# UCirKitUserStudy4.net
KiCad netlist of a schematic drawn in EAGLE
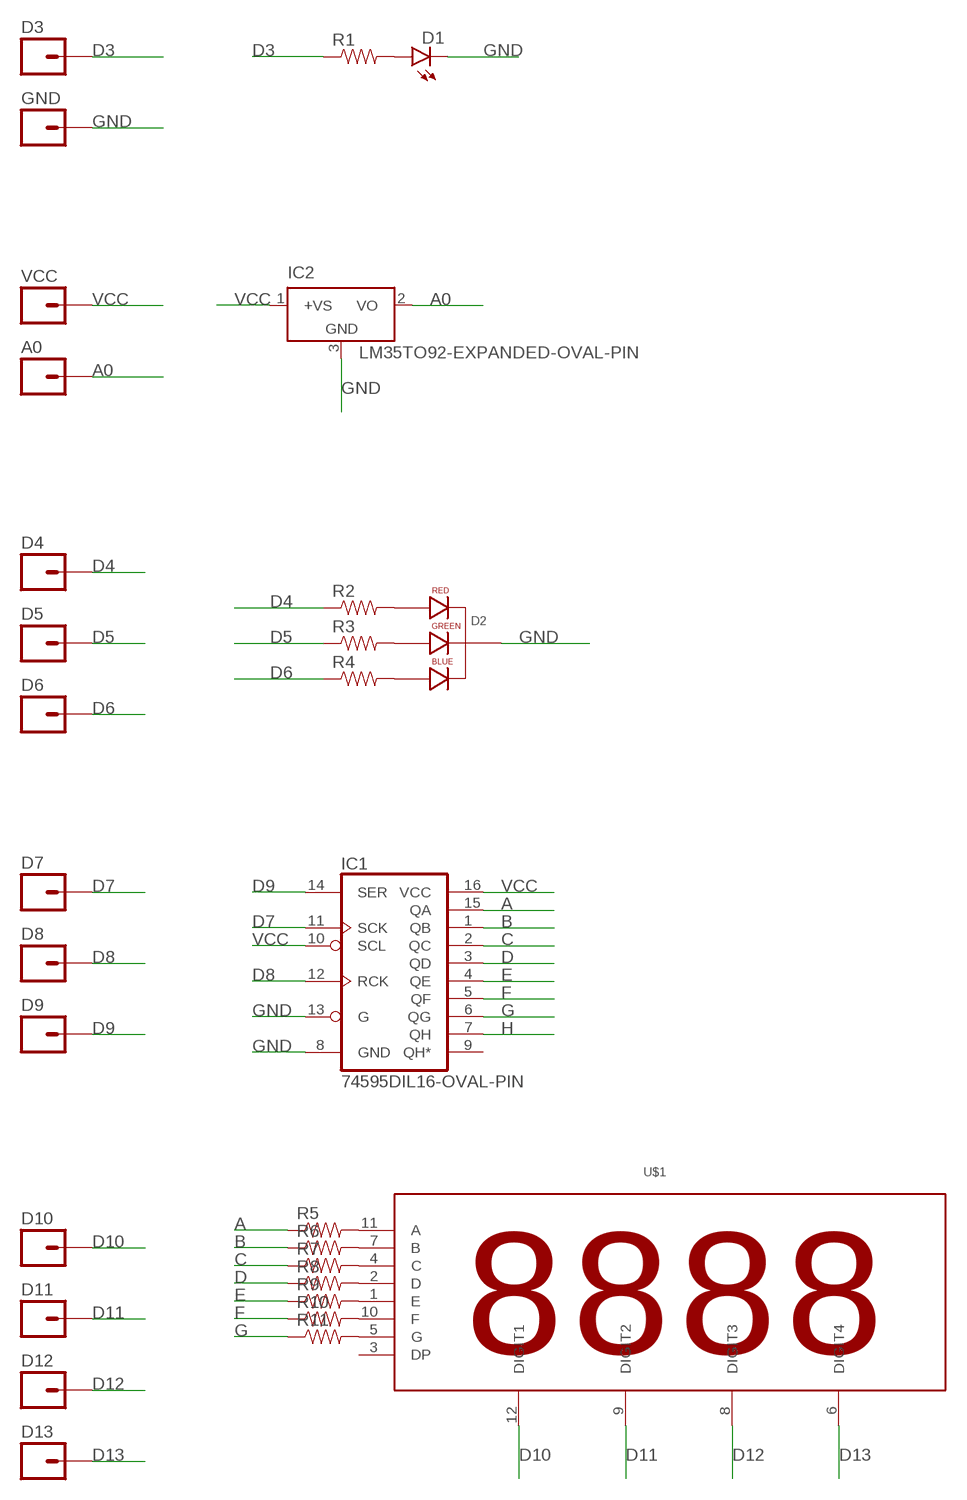
[diagram p0: schematic, sheet 1]

(export (version "E")
  (design (tool "Eeschema 10.0.6"))
  (components
    (comp (ref "A0")
      (value "M01OVAL_PIN")
      (footprint "eagle-import:1X01_OVAL_PIN")
      (libsource (lib "eagle-import") (part "M01OVAL_PIN"))
    )
    (comp (ref "D1")
      (value "LEDLED3MM-EXPANDED-OVAL-PIN")
      (footprint "eagle-import:LED3MM-EXPANDED-OVAL-PIN")
      (libsource (lib "eagle-import") (part "LEDLED3MM-EXPANDED-OVAL-PIN"))
    )
    (comp (ref "D2")
      (value "LED-RGB-CC-THRULED-RGB-THRU-EXPANDED-OVAL-PIN")
      (footprint "eagle-import:LED-RGB-THRU-EXPANDED-OVAL-PIN")
      (libsource (lib "eagle-import") (part "LED-RGB-CC-THRULED-RGB-THRU-EXPANDED-OVAL-PIN"))
    )
    (comp (ref "D3")
      (value "M01OVAL_PIN")
      (footprint "eagle-import:1X01_OVAL_PIN")
      (libsource (lib "eagle-import") (part "M01OVAL_PIN"))
    )
    (comp (ref "D4")
      (value "M01OVAL_PIN")
      (footprint "eagle-import:1X01_OVAL_PIN")
      (libsource (lib "eagle-import") (part "M01OVAL_PIN"))
    )
    (comp (ref "D5")
      (value "M01OVAL_PIN")
      (footprint "eagle-import:1X01_OVAL_PIN")
      (libsource (lib "eagle-import") (part "M01OVAL_PIN"))
    )
    (comp (ref "D6")
      (value "M01OVAL_PIN")
      (footprint "eagle-import:1X01_OVAL_PIN")
      (libsource (lib "eagle-import") (part "M01OVAL_PIN"))
    )
    (comp (ref "D7")
      (value "M01OVAL_PIN")
      (footprint "eagle-import:1X01_OVAL_PIN")
      (libsource (lib "eagle-import") (part "M01OVAL_PIN"))
    )
    (comp (ref "D8")
      (value "M01OVAL_PIN")
      (footprint "eagle-import:1X01_OVAL_PIN")
      (libsource (lib "eagle-import") (part "M01OVAL_PIN"))
    )
    (comp (ref "D9")
      (value "M01OVAL_PIN")
      (footprint "eagle-import:1X01_OVAL_PIN")
      (libsource (lib "eagle-import") (part "M01OVAL_PIN"))
    )
    (comp (ref "D10")
      (value "M01OVAL_PIN")
      (footprint "eagle-import:1X01_OVAL_PIN")
      (libsource (lib "eagle-import") (part "M01OVAL_PIN"))
    )
    (comp (ref "D11")
      (value "M01OVAL_PIN")
      (footprint "eagle-import:1X01_OVAL_PIN")
      (libsource (lib "eagle-import") (part "M01OVAL_PIN"))
    )
    (comp (ref "D12")
      (value "M01OVAL_PIN")
      (footprint "eagle-import:1X01_OVAL_PIN")
      (libsource (lib "eagle-import") (part "M01OVAL_PIN"))
    )
    (comp (ref "D13")
      (value "M01OVAL_PIN")
      (footprint "eagle-import:1X01_OVAL_PIN")
      (libsource (lib "eagle-import") (part "M01OVAL_PIN"))
    )
    (comp (ref "GND")
      (value "M01OVAL_PIN")
      (footprint "eagle-import:1X01_OVAL_PIN")
      (libsource (lib "eagle-import") (part "M01OVAL_PIN"))
    )
    (comp (ref "IC1")
      (value "74595DIL16-OVAL-PIN")
      (footprint "eagle-import:DIL16-OVAL-PIN")
      (libsource (lib "eagle-import") (part "74595DIL16-OVAL-PIN"))
    )
    (comp (ref "IC2")
      (value "LM35TO92-EXPANDED-OVAL-PIN")
      (footprint "eagle-import:TO92-EXPANDED-OVAL-PIN")
      (libsource (lib "eagle-import") (part "LM35TO92-EXPANDED-OVAL-PIN"))
    )
    (comp (ref "R1")
      (value "1KOHM-1/4W-1%(PTH)PTH-EXPANDED-OVAL-PIN")
      (footprint "eagle-import:PTH-EXPANDED-OVAL-PIN")
      (libsource (lib "eagle-import") (part "1KOHM-1/4W-1%(PTH)PTH-EXPANDED-OVAL-PIN"))
    )
    (comp (ref "R2")
      (value "1KOHM-1/4W-1%(PTH)PTH-EXPANDED-OVAL-PIN")
      (footprint "eagle-import:PTH-EXPANDED-OVAL-PIN")
      (libsource (lib "eagle-import") (part "1KOHM-1/4W-1%(PTH)PTH-EXPANDED-OVAL-PIN"))
    )
    (comp (ref "R3")
      (value "1KOHM-1/4W-1%(PTH)PTH-EXPANDED-OVAL-PIN")
      (footprint "eagle-import:PTH-EXPANDED-OVAL-PIN")
      (libsource (lib "eagle-import") (part "1KOHM-1/4W-1%(PTH)PTH-EXPANDED-OVAL-PIN"))
    )
    (comp (ref "R4")
      (value "1KOHM-1/4W-1%(PTH)PTH-EXPANDED-OVAL-PIN")
      (footprint "eagle-import:PTH-EXPANDED-OVAL-PIN")
      (libsource (lib "eagle-import") (part "1KOHM-1/4W-1%(PTH)PTH-EXPANDED-OVAL-PIN"))
    )
    (comp (ref "R5")
      (value "1KOHM-1/4W-1%(PTH)PTH-EXPANDED-OVAL-PIN")
      (footprint "eagle-import:PTH-EXPANDED-OVAL-PIN")
      (libsource (lib "eagle-import") (part "1KOHM-1/4W-1%(PTH)PTH-EXPANDED-OVAL-PIN"))
    )
    (comp (ref "R6")
      (value "1KOHM-1/4W-1%(PTH)PTH-EXPANDED-OVAL-PIN")
      (footprint "eagle-import:PTH-EXPANDED-OVAL-PIN")
      (libsource (lib "eagle-import") (part "1KOHM-1/4W-1%(PTH)PTH-EXPANDED-OVAL-PIN"))
    )
    (comp (ref "R7")
      (value "1KOHM-1/4W-1%(PTH)PTH-EXPANDED-OVAL-PIN")
      (footprint "eagle-import:PTH-EXPANDED-OVAL-PIN")
      (libsource (lib "eagle-import") (part "1KOHM-1/4W-1%(PTH)PTH-EXPANDED-OVAL-PIN"))
    )
    (comp (ref "R8")
      (value "1KOHM-1/4W-1%(PTH)PTH-EXPANDED-OVAL-PIN")
      (footprint "eagle-import:PTH-EXPANDED-OVAL-PIN")
      (libsource (lib "eagle-import") (part "1KOHM-1/4W-1%(PTH)PTH-EXPANDED-OVAL-PIN"))
    )
    (comp (ref "R9")
      (value "1KOHM-1/4W-1%(PTH)PTH-EXPANDED-OVAL-PIN")
      (footprint "eagle-import:PTH-EXPANDED-OVAL-PIN")
      (libsource (lib "eagle-import") (part "1KOHM-1/4W-1%(PTH)PTH-EXPANDED-OVAL-PIN"))
    )
    (comp (ref "R10")
      (value "1KOHM-1/4W-1%(PTH)PTH-EXPANDED-OVAL-PIN")
      (footprint "eagle-import:PTH-EXPANDED-OVAL-PIN")
      (libsource (lib "eagle-import") (part "1KOHM-1/4W-1%(PTH)PTH-EXPANDED-OVAL-PIN"))
    )
    (comp (ref "R11")
      (value "1KOHM-1/4W-1%(PTH)PTH-EXPANDED-OVAL-PIN")
      (footprint "eagle-import:PTH-EXPANDED-OVAL-PIN")
      (libsource (lib "eagle-import") (part "1KOHM-1/4W-1%(PTH)PTH-EXPANDED-OVAL-PIN"))
    )
    (comp (ref "U$1")
      (value "4DIGIT_SEVEN_SEGMENT4DIGIT_SEVEN_SEGMENT_OVAL_PIN")
      (footprint "eagle-import:4DIGIT_SEVEN_SEGMENT_OVAL_PIN")
      (libsource (lib "eagle-import") (part "4DIGIT_SEVEN_SEGMENT4DIGIT_SEVEN_SEGMENT_OVAL_PIN"))
    )
    (comp (ref "VCC")
      (value "M01OVAL_PIN")
      (footprint "eagle-import:1X01_OVAL_PIN")
      (libsource (lib "eagle-import") (part "M01OVAL_PIN"))
    )
  )
  (nets
    (net (code "1") (name "/A") (class "Default")
      (node (ref "IC1") (pin "15") (pinfunction "QA_15") (pintype "tri_state"))
      (node (ref "R5") (pin "P$1") (pinfunction "1_P$1") (pintype "passive"))
    )
    (net (code "2") (name "/A0") (class "Default")
      (node (ref "A0") (pin "1") (pinfunction "1_1") (pintype "passive"))
      (node (ref "IC2") (pin "2") (pinfunction "VO_2") (pintype "input"))
    )
    (net (code "3") (name "/B") (class "Default")
      (node (ref "IC1") (pin "1") (pinfunction "QB_1") (pintype "tri_state"))
      (node (ref "R6") (pin "P$1") (pinfunction "1_P$1") (pintype "passive"))
    )
    (net (code "4") (name "/C") (class "Default")
      (node (ref "IC1") (pin "2") (pinfunction "QC_2") (pintype "tri_state"))
      (node (ref "R7") (pin "P$1") (pinfunction "1_P$1") (pintype "passive"))
    )
    (net (code "5") (name "/D") (class "Default")
      (node (ref "IC1") (pin "3") (pinfunction "QD_3") (pintype "tri_state"))
      (node (ref "R8") (pin "P$1") (pinfunction "1_P$1") (pintype "passive"))
    )
    (net (code "6") (name "/D3") (class "Default")
      (node (ref "D3") (pin "1") (pinfunction "1_1") (pintype "passive"))
      (node (ref "R1") (pin "P$1") (pinfunction "1_P$1") (pintype "passive"))
    )
    (net (code "7") (name "/D4") (class "Default")
      (node (ref "D4") (pin "1") (pinfunction "1_1") (pintype "passive"))
      (node (ref "R2") (pin "P$1") (pinfunction "1_P$1") (pintype "passive"))
    )
    (net (code "8") (name "/D5") (class "Default")
      (node (ref "D5") (pin "1") (pinfunction "1_1") (pintype "passive"))
      (node (ref "R3") (pin "P$1") (pinfunction "1_P$1") (pintype "passive"))
    )
    (net (code "9") (name "/D6") (class "Default")
      (node (ref "D6") (pin "1") (pinfunction "1_1") (pintype "passive"))
      (node (ref "R4") (pin "P$1") (pinfunction "1_P$1") (pintype "passive"))
    )
    (net (code "10") (name "/D7") (class "Default")
      (node (ref "D7") (pin "1") (pinfunction "1_1") (pintype "passive"))
      (node (ref "IC1") (pin "11") (pinfunction "SCK_11") (pintype "input"))
    )
    (net (code "11") (name "/D8") (class "Default")
      (node (ref "D8") (pin "1") (pinfunction "1_1") (pintype "passive"))
      (node (ref "IC1") (pin "12") (pinfunction "RCK_12") (pintype "input"))
    )
    (net (code "12") (name "/D9") (class "Default")
      (node (ref "D9") (pin "1") (pinfunction "1_1") (pintype "passive"))
      (node (ref "IC1") (pin "14") (pinfunction "SER_14") (pintype "input"))
    )
    (net (code "13") (name "/D10") (class "Default")
      (node (ref "D10") (pin "1") (pinfunction "1_1") (pintype "passive"))
      (node (ref "U$1") (pin "12") (pinfunction "DIGIT1_12") (pintype "bidirectional"))
    )
    (net (code "14") (name "/D11") (class "Default")
      (node (ref "D11") (pin "1") (pinfunction "1_1") (pintype "passive"))
      (node (ref "U$1") (pin "9") (pinfunction "DIGIT2_9") (pintype "bidirectional"))
    )
    (net (code "15") (name "/D12") (class "Default")
      (node (ref "D12") (pin "1") (pinfunction "1_1") (pintype "passive"))
      (node (ref "U$1") (pin "8") (pinfunction "DIGIT3_8") (pintype "bidirectional"))
    )
    (net (code "16") (name "/D13") (class "Default")
      (node (ref "D13") (pin "1") (pinfunction "1_1") (pintype "passive"))
      (node (ref "U$1") (pin "6") (pinfunction "DIGIT4_6") (pintype "bidirectional"))
    )
    (net (code "17") (name "/E") (class "Default")
      (node (ref "IC1") (pin "4") (pinfunction "QE_4") (pintype "tri_state"))
      (node (ref "R9") (pin "P$1") (pinfunction "1_P$1") (pintype "passive"))
    )
    (net (code "18") (name "/F") (class "Default")
      (node (ref "IC1") (pin "5") (pinfunction "QF_5") (pintype "tri_state"))
      (node (ref "R10") (pin "P$1") (pinfunction "1_P$1") (pintype "passive"))
    )
    (net (code "19") (name "/G") (class "Default")
      (node (ref "IC1") (pin "6") (pinfunction "QG_6") (pintype "tri_state"))
      (node (ref "R11") (pin "P$1") (pinfunction "1_P$1") (pintype "passive"))
    )
    (net (code "20") (name "/GND") (class "Default")
      (node (ref "D1") (pin "K") (pinfunction "C_K") (pintype "passive"))
      (node (ref "D2") (pin "2") (pinfunction "CATHODE_2") (pintype "bidirectional"))
      (node (ref "GND") (pin "1") (pinfunction "1_1") (pintype "passive"))
      (node (ref "IC1") (pin "13") (pinfunction "G_13") (pintype "input"))
      (node (ref "IC1") (pin "8") (pinfunction "GND_8") (pintype "power_in"))
      (node (ref "IC2") (pin "3") (pinfunction "GND_3") (pintype "power_in"))
    )
    (net (code "21") (name "/H") (class "Default")
      (node (ref "IC1") (pin "7") (pinfunction "QH_7") (pintype "tri_state"))
    )
    (net (code "22") (name "/VCC") (class "Default")
      (node (ref "IC1") (pin "10") (pinfunction "SCL_10") (pintype "input"))
      (node (ref "IC1") (pin "16") (pinfunction "VCC_16") (pintype "power_in"))
      (node (ref "IC2") (pin "1") (pinfunction "+VS_1") (pintype "input"))
      (node (ref "VCC") (pin "1") (pinfunction "1_1") (pintype "passive"))
    )
    (net (code "23") (name "Net-(D2-BLUE_CATHODE)") (class "Default")
      (node (ref "D2") (pin "4") (pinfunction "BLUE_CATHODE_4") (pintype "bidirectional"))
      (node (ref "R4") (pin "P$2") (pinfunction "2_P$2") (pintype "passive"))
    )
    (net (code "24") (name "Net-(D2-GREEN_CATHODE)") (class "Default")
      (node (ref "D2") (pin "3") (pinfunction "GREEN_CATHODE_3") (pintype "bidirectional"))
      (node (ref "R3") (pin "P$2") (pinfunction "2_P$2") (pintype "passive"))
    )
    (net (code "25") (name "Net-(D2-RED_CATHODE)") (class "Default")
      (node (ref "D2") (pin "1") (pinfunction "RED_CATHODE_1") (pintype "bidirectional"))
      (node (ref "R2") (pin "P$2") (pinfunction "2_P$2") (pintype "passive"))
    )
    (net (code "26") (name "Net-(R1-2)") (class "Default")
      (node (ref "D1") (pin "A") (pinfunction "A_A") (pintype "passive"))
      (node (ref "R1") (pin "P$2") (pinfunction "2_P$2") (pintype "passive"))
    )
    (net (code "27") (name "Net-(R5-2)") (class "Default")
      (node (ref "R5") (pin "P$2") (pinfunction "2_P$2") (pintype "passive"))
      (node (ref "U$1") (pin "11") (pinfunction "A_11") (pintype "bidirectional"))
    )
    (net (code "28") (name "Net-(R6-2)") (class "Default")
      (node (ref "R6") (pin "P$2") (pinfunction "2_P$2") (pintype "passive"))
      (node (ref "U$1") (pin "7") (pinfunction "B_7") (pintype "bidirectional"))
    )
    (net (code "29") (name "Net-(R7-2)") (class "Default")
      (node (ref "R7") (pin "P$2") (pinfunction "2_P$2") (pintype "passive"))
      (node (ref "U$1") (pin "4") (pinfunction "C_4") (pintype "bidirectional"))
    )
    (net (code "30") (name "Net-(R8-2)") (class "Default")
      (node (ref "R8") (pin "P$2") (pinfunction "2_P$2") (pintype "passive"))
      (node (ref "U$1") (pin "2") (pinfunction "D_2") (pintype "bidirectional"))
    )
    (net (code "31") (name "Net-(R9-2)") (class "Default")
      (node (ref "R9") (pin "P$2") (pinfunction "2_P$2") (pintype "passive"))
      (node (ref "U$1") (pin "1") (pinfunction "E_1") (pintype "bidirectional"))
    )
    (net (code "32") (name "Net-(R10-2)") (class "Default")
      (node (ref "R10") (pin "P$2") (pinfunction "2_P$2") (pintype "passive"))
      (node (ref "U$1") (pin "10") (pinfunction "F_10") (pintype "bidirectional"))
    )
    (net (code "33") (name "Net-(R11-2)") (class "Default")
      (node (ref "R11") (pin "P$2") (pinfunction "2_P$2") (pintype "passive"))
      (node (ref "U$1") (pin "5") (pinfunction "G_5") (pintype "bidirectional"))
    )
    (net (code "34") (name "unconnected-(IC1-QH*-Pad9)") (class "Default")
      (node (ref "IC1") (pin "9") (pinfunction "QH*_9") (pintype "tri_state"))
    )
    (net (code "35") (name "unconnected-(U$1-DP-Pad3)") (class "Default")
      (node (ref "U$1") (pin "3") (pinfunction "DP_3") (pintype "bidirectional"))
    )
  )
)
